# ServoConnect.net
KiCad netlist of a schematic drawn in Altium Designer
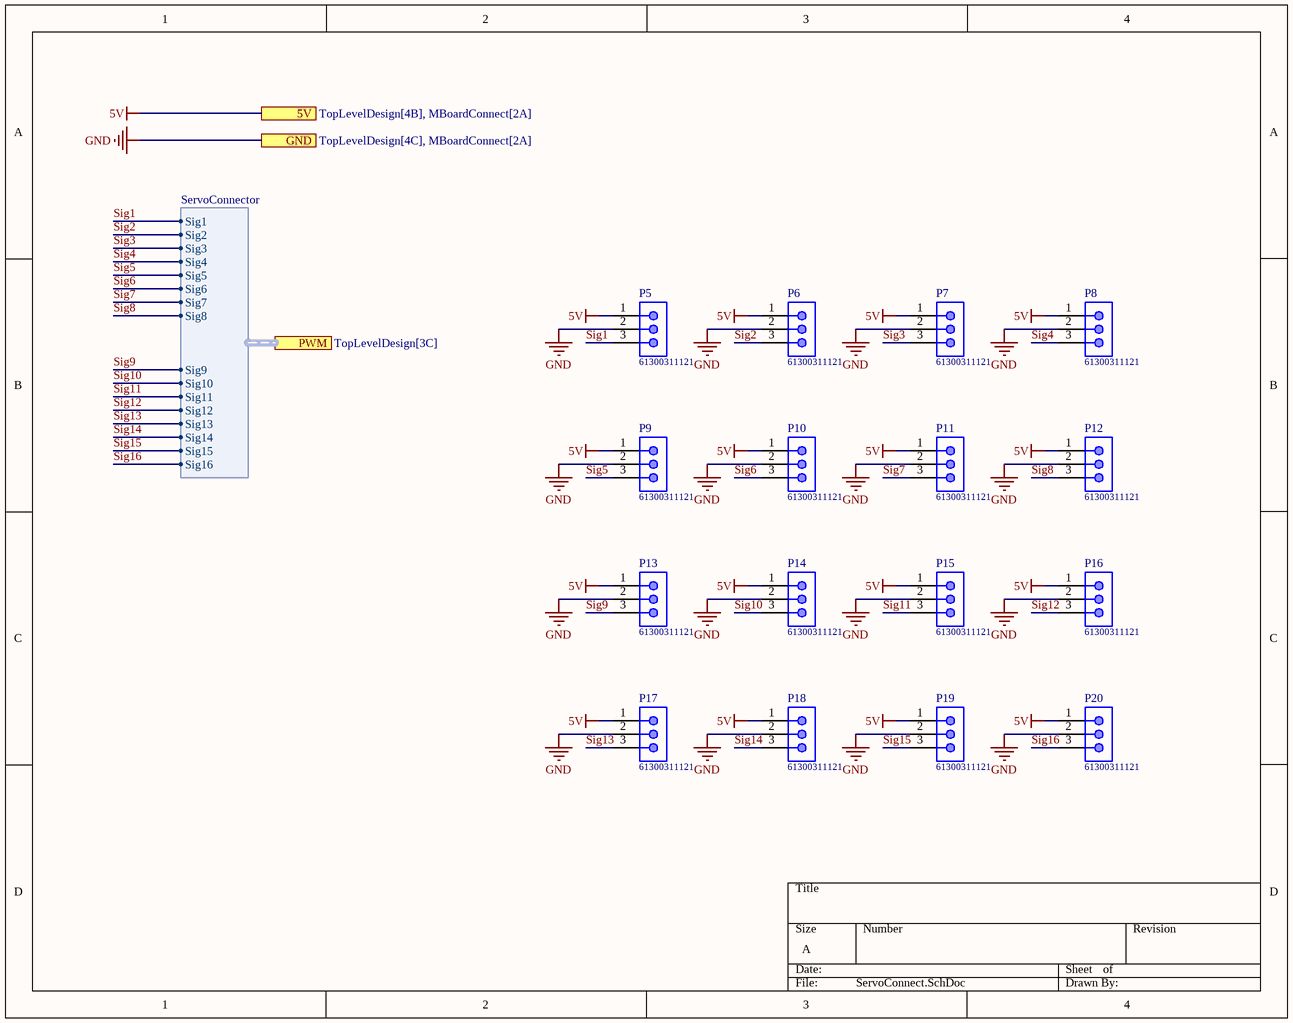
[diagram p0: ServoConnect.SchDoc]

(export (version "E")
  (design (tool "Eeschema 10.0.6"))
  (components
    (comp (ref "P5")
      (value "61300311121")
      (footprint "61300311121")
      (description "WR-PHD Pin Header, THT, pitch 2.54mm, Single Row, Vertical, 3p")
      (fields (field (name "MANUFACTURER") "Wurth Elektronik"))
      (libsource (lib "Tin Tran") (part "61300311121"))
    )
    (comp (ref "P6")
      (value "61300311121")
      (footprint "61300311121")
      (description "WR-PHD Pin Header, THT, pitch 2.54mm, Single Row, Vertical, 3p")
      (fields (field (name "MANUFACTURER") "Wurth Elektronik"))
      (libsource (lib "Tin Tran") (part "61300311121"))
    )
    (comp (ref "P7")
      (value "61300311121")
      (footprint "61300311121")
      (description "WR-PHD Pin Header, THT, pitch 2.54mm, Single Row, Vertical, 3p")
      (fields (field (name "MANUFACTURER") "Wurth Elektronik"))
      (libsource (lib "Tin Tran") (part "61300311121"))
    )
    (comp (ref "P8")
      (value "61300311121")
      (footprint "61300311121")
      (description "WR-PHD Pin Header, THT, pitch 2.54mm, Single Row, Vertical, 3p")
      (fields (field (name "MANUFACTURER") "Wurth Elektronik"))
      (libsource (lib "Tin Tran") (part "61300311121"))
    )
    (comp (ref "P9")
      (value "61300311121")
      (footprint "61300311121")
      (description "WR-PHD Pin Header, THT, pitch 2.54mm, Single Row, Vertical, 3p")
      (fields (field (name "MANUFACTURER") "Wurth Elektronik"))
      (libsource (lib "Tin Tran") (part "61300311121"))
    )
    (comp (ref "P10")
      (value "61300311121")
      (footprint "61300311121")
      (description "WR-PHD Pin Header, THT, pitch 2.54mm, Single Row, Vertical, 3p")
      (fields (field (name "MANUFACTURER") "Wurth Elektronik"))
      (libsource (lib "Tin Tran") (part "61300311121"))
    )
    (comp (ref "P11")
      (value "61300311121")
      (footprint "61300311121")
      (description "WR-PHD Pin Header, THT, pitch 2.54mm, Single Row, Vertical, 3p")
      (fields (field (name "MANUFACTURER") "Wurth Elektronik"))
      (libsource (lib "Tin Tran") (part "61300311121"))
    )
    (comp (ref "P12")
      (value "61300311121")
      (footprint "61300311121")
      (description "WR-PHD Pin Header, THT, pitch 2.54mm, Single Row, Vertical, 3p")
      (fields (field (name "MANUFACTURER") "Wurth Elektronik"))
      (libsource (lib "Tin Tran") (part "61300311121"))
    )
    (comp (ref "P13")
      (value "61300311121")
      (footprint "61300311121")
      (description "WR-PHD Pin Header, THT, pitch 2.54mm, Single Row, Vertical, 3p")
      (fields (field (name "MANUFACTURER") "Wurth Elektronik"))
      (libsource (lib "Tin Tran") (part "61300311121"))
    )
    (comp (ref "P14")
      (value "61300311121")
      (footprint "61300311121")
      (description "WR-PHD Pin Header, THT, pitch 2.54mm, Single Row, Vertical, 3p")
      (fields (field (name "MANUFACTURER") "Wurth Elektronik"))
      (libsource (lib "Tin Tran") (part "61300311121"))
    )
    (comp (ref "P15")
      (value "61300311121")
      (footprint "61300311121")
      (description "WR-PHD Pin Header, THT, pitch 2.54mm, Single Row, Vertical, 3p")
      (fields (field (name "MANUFACTURER") "Wurth Elektronik"))
      (libsource (lib "Tin Tran") (part "61300311121"))
    )
    (comp (ref "P16")
      (value "61300311121")
      (footprint "61300311121")
      (description "WR-PHD Pin Header, THT, pitch 2.54mm, Single Row, Vertical, 3p")
      (fields (field (name "MANUFACTURER") "Wurth Elektronik"))
      (libsource (lib "Tin Tran") (part "61300311121"))
    )
    (comp (ref "P17")
      (value "61300311121")
      (footprint "61300311121")
      (description "WR-PHD Pin Header, THT, pitch 2.54mm, Single Row, Vertical, 3p")
      (fields (field (name "MANUFACTURER") "Wurth Elektronik"))
      (libsource (lib "Tin Tran") (part "61300311121"))
    )
    (comp (ref "P18")
      (value "61300311121")
      (footprint "61300311121")
      (description "WR-PHD Pin Header, THT, pitch 2.54mm, Single Row, Vertical, 3p")
      (fields (field (name "MANUFACTURER") "Wurth Elektronik"))
      (libsource (lib "Tin Tran") (part "61300311121"))
    )
    (comp (ref "P19")
      (value "61300311121")
      (footprint "61300311121")
      (description "WR-PHD Pin Header, THT, pitch 2.54mm, Single Row, Vertical, 3p")
      (fields (field (name "MANUFACTURER") "Wurth Elektronik"))
      (libsource (lib "Tin Tran") (part "61300311121"))
    )
    (comp (ref "P20")
      (value "61300311121")
      (footprint "61300311121")
      (description "WR-PHD Pin Header, THT, pitch 2.54mm, Single Row, Vertical, 3p")
      (fields (field (name "MANUFACTURER") "Wurth Elektronik"))
      (libsource (lib "Tin Tran") (part "61300311121"))
    )
  )
  (nets
    (net (code "2") (name "/Sig1") (class "Default")
      (node (ref "P5") (pin "3") (pinfunction "3_3") (pintype "passive"))
    )
    (net (code "3") (name "/Sig2") (class "Default")
      (node (ref "P6") (pin "3") (pinfunction "3_3") (pintype "passive"))
    )
    (net (code "4") (name "/Sig3") (class "Default")
      (node (ref "P7") (pin "3") (pinfunction "3_3") (pintype "passive"))
    )
    (net (code "5") (name "/Sig4") (class "Default")
      (node (ref "P8") (pin "3") (pinfunction "3_3") (pintype "passive"))
    )
    (net (code "6") (name "/Sig5") (class "Default")
      (node (ref "P9") (pin "3") (pinfunction "3_3") (pintype "passive"))
    )
    (net (code "7") (name "/Sig6") (class "Default")
      (node (ref "P10") (pin "3") (pinfunction "3_3") (pintype "passive"))
    )
    (net (code "8") (name "/Sig7") (class "Default")
      (node (ref "P11") (pin "3") (pinfunction "3_3") (pintype "passive"))
    )
    (net (code "9") (name "/Sig8") (class "Default")
      (node (ref "P12") (pin "3") (pinfunction "3_3") (pintype "passive"))
    )
    (net (code "10") (name "/Sig9") (class "Default")
      (node (ref "P13") (pin "3") (pinfunction "3_3") (pintype "passive"))
    )
    (net (code "11") (name "/Sig10") (class "Default")
      (node (ref "P14") (pin "3") (pinfunction "3_3") (pintype "passive"))
    )
    (net (code "12") (name "/Sig11") (class "Default")
      (node (ref "P15") (pin "3") (pinfunction "3_3") (pintype "passive"))
    )
    (net (code "13") (name "/Sig12") (class "Default")
      (node (ref "P16") (pin "3") (pinfunction "3_3") (pintype "passive"))
    )
    (net (code "14") (name "/Sig13") (class "Default")
      (node (ref "P17") (pin "3") (pinfunction "3_3") (pintype "passive"))
    )
    (net (code "15") (name "/Sig14") (class "Default")
      (node (ref "P18") (pin "3") (pinfunction "3_3") (pintype "passive"))
    )
    (net (code "16") (name "/Sig15") (class "Default")
      (node (ref "P19") (pin "3") (pinfunction "3_3") (pintype "passive"))
    )
    (net (code "17") (name "/Sig16") (class "Default")
      (node (ref "P20") (pin "3") (pinfunction "3_3") (pintype "passive"))
    )
    (net (code "19") (name "5V") (class "Default")
      (node (ref "P10") (pin "1") (pinfunction "1_1") (pintype "passive"))
      (node (ref "P11") (pin "1") (pinfunction "1_1") (pintype "passive"))
      (node (ref "P12") (pin "1") (pinfunction "1_1") (pintype "passive"))
      (node (ref "P13") (pin "1") (pinfunction "1_1") (pintype "passive"))
      (node (ref "P14") (pin "1") (pinfunction "1_1") (pintype "passive"))
      (node (ref "P15") (pin "1") (pinfunction "1_1") (pintype "passive"))
      (node (ref "P16") (pin "1") (pinfunction "1_1") (pintype "passive"))
      (node (ref "P17") (pin "1") (pinfunction "1_1") (pintype "passive"))
      (node (ref "P18") (pin "1") (pinfunction "1_1") (pintype "passive"))
      (node (ref "P19") (pin "1") (pinfunction "1_1") (pintype "passive"))
      (node (ref "P20") (pin "1") (pinfunction "1_1") (pintype "passive"))
      (node (ref "P5") (pin "1") (pinfunction "1_1") (pintype "passive"))
      (node (ref "P6") (pin "1") (pinfunction "1_1") (pintype "passive"))
      (node (ref "P7") (pin "1") (pinfunction "1_1") (pintype "passive"))
      (node (ref "P8") (pin "1") (pinfunction "1_1") (pintype "passive"))
      (node (ref "P9") (pin "1") (pinfunction "1_1") (pintype "passive"))
    )
    (net (code "20") (name "GND") (class "Default")
      (node (ref "P10") (pin "2") (pinfunction "2_2") (pintype "passive"))
      (node (ref "P11") (pin "2") (pinfunction "2_2") (pintype "passive"))
      (node (ref "P12") (pin "2") (pinfunction "2_2") (pintype "passive"))
      (node (ref "P13") (pin "2") (pinfunction "2_2") (pintype "passive"))
      (node (ref "P14") (pin "2") (pinfunction "2_2") (pintype "passive"))
      (node (ref "P15") (pin "2") (pinfunction "2_2") (pintype "passive"))
      (node (ref "P16") (pin "2") (pinfunction "2_2") (pintype "passive"))
      (node (ref "P17") (pin "2") (pinfunction "2_2") (pintype "passive"))
      (node (ref "P18") (pin "2") (pinfunction "2_2") (pintype "passive"))
      (node (ref "P19") (pin "2") (pinfunction "2_2") (pintype "passive"))
      (node (ref "P20") (pin "2") (pinfunction "2_2") (pintype "passive"))
      (node (ref "P5") (pin "2") (pinfunction "2_2") (pintype "passive"))
      (node (ref "P6") (pin "2") (pinfunction "2_2") (pintype "passive"))
      (node (ref "P7") (pin "2") (pinfunction "2_2") (pintype "passive"))
      (node (ref "P8") (pin "2") (pinfunction "2_2") (pintype "passive"))
      (node (ref "P9") (pin "2") (pinfunction "2_2") (pintype "passive"))
    )
  )
)
